# Final3_uptodate.net
KiCad netlist of a schematic drawn in EAGLE
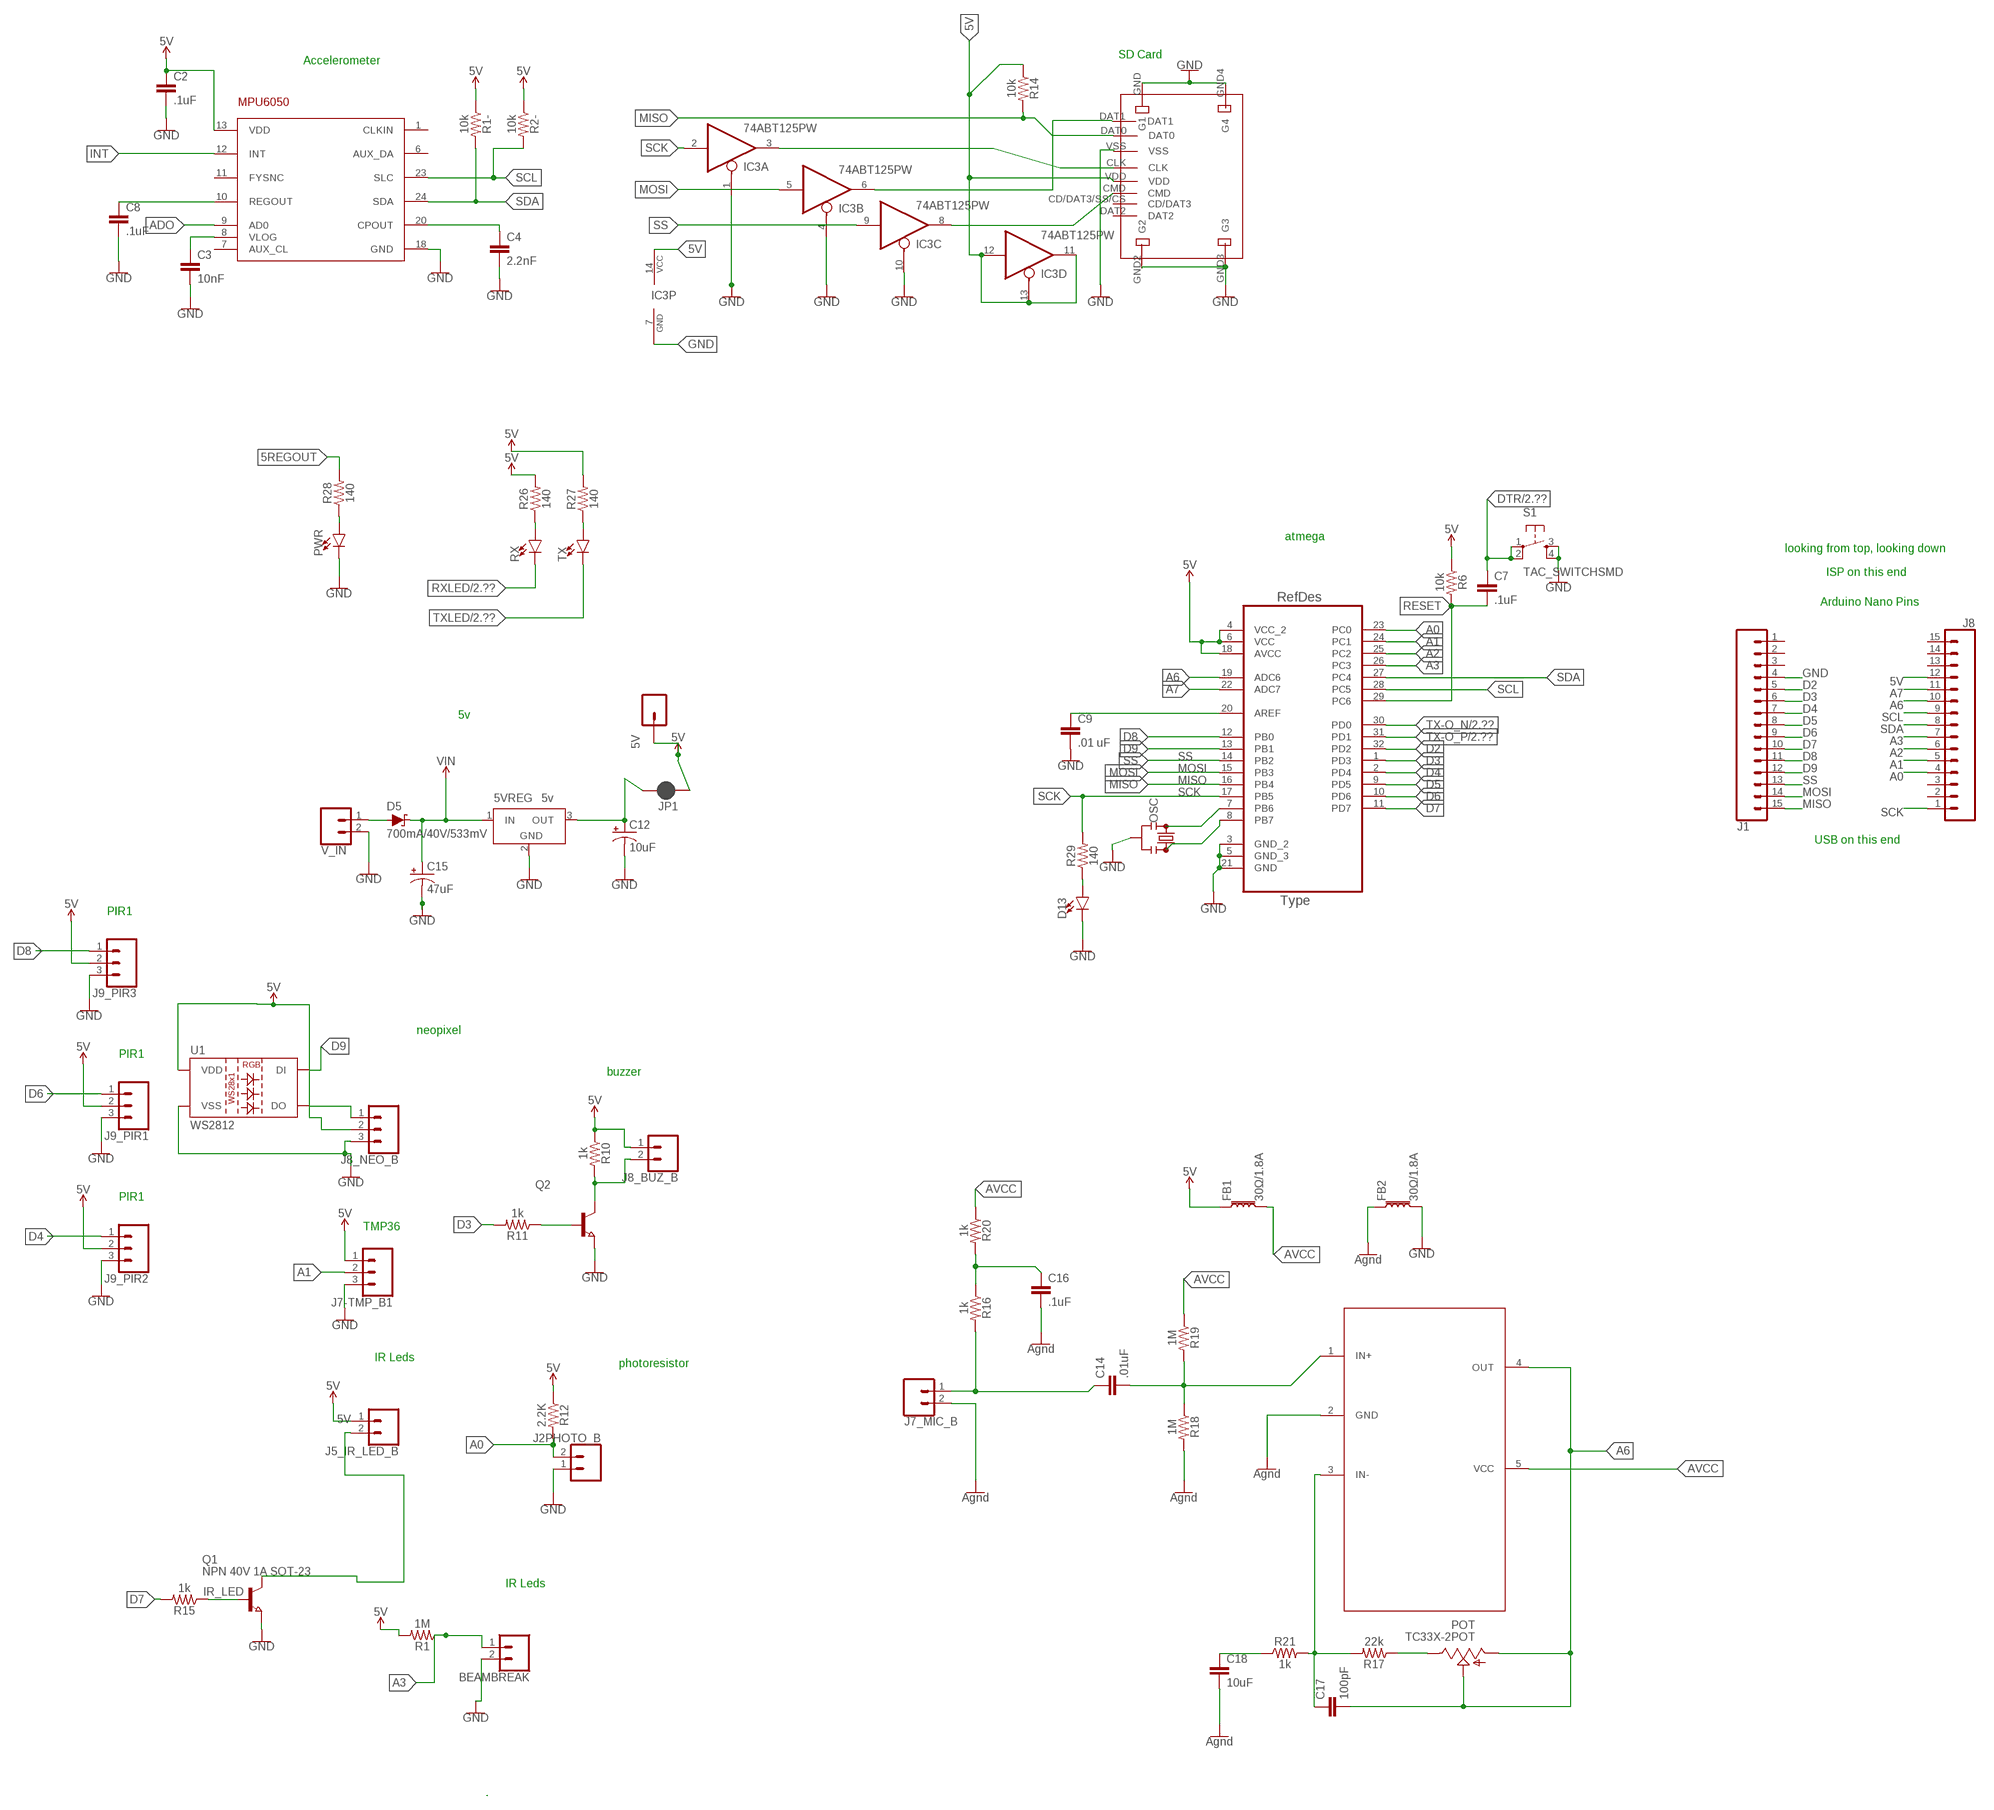
[diagram p0: schematic, sheet 1]
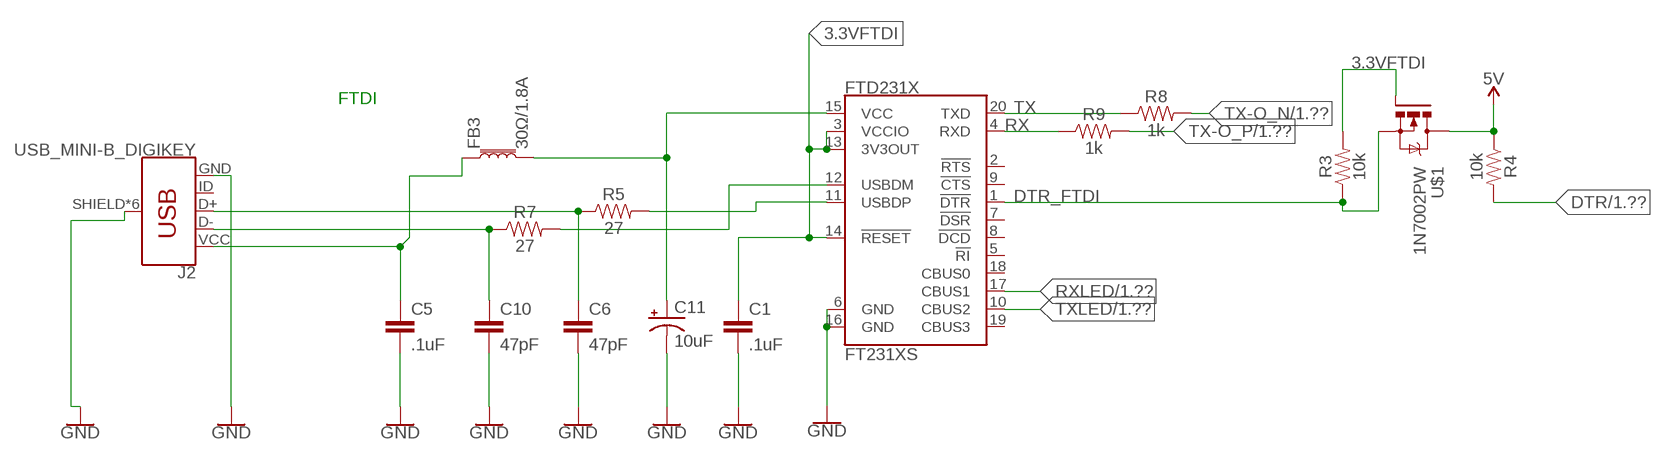
[diagram p1: schematic, sheet 2]

(export (version "E")
  (design (tool "Eeschema 10.0.6"))
  (components
    (comp (ref "5V")
      (value "CONN_01")
      (footprint "eagle-import:1X01")
      (libsource (lib "eagle-import") (part "CONN_01"))
    )
    (comp (ref "5VREG")
      (value "5v")
      (footprint "eagle-import:SOT223")
      (fields (field (name "MPN") "LT1129CST-5#PBF"))
      (libsource (lib "eagle-import") (part "LT1129CST5"))
    )
    (comp (ref "AMP")
      (value "MAX4466KS")
      (footprint "eagle-import:SC70-5")
      (libsource (lib "eagle-import") (part "MAX4466KS"))
    )
    (comp (ref "ATMEGA328P-AU")
      (value "ATMEGA328P-AU")
      (footprint "eagle-import:QFP80P900X900X120-32N")
      (libsource (lib "eagle-import") (part "ATMEGA328P-AU"))
    )
    (comp (ref "BEAMBREAK")
      (value "CONN_02LOCK")
      (footprint "eagle-import:1X02_LOCK")
      (libsource (lib "eagle-import") (part "CONN_02LOCK"))
    )
    (comp (ref "C2")
      (value ".1uF")
      (footprint "eagle-import:0402-CAP")
      (libsource (lib "eagle-import") (part ".22UF-CER"))
    )
    (comp (ref "C3")
      (value "10nF")
      (footprint "eagle-import:0402-CAP")
      (libsource (lib "eagle-import") (part ".22UF-CER"))
    )
    (comp (ref "C4")
      (value "2.2nF")
      (footprint "eagle-import:0402-CAP")
      (libsource (lib "eagle-import") (part ".22UF-CER"))
    )
    (comp (ref "C7")
      (value ".1uF")
      (footprint "eagle-import:0402-CAP")
      (libsource (lib "eagle-import") (part ".22UF-CER"))
    )
    (comp (ref "C8")
      (value ".1uF")
      (footprint "eagle-import:0402-CAP")
      (libsource (lib "eagle-import") (part ".22UF-CER"))
    )
    (comp (ref "C9")
      (value ".01 uF")
      (footprint "eagle-import:0402-CAP")
      (libsource (lib "eagle-import") (part ".22UF-CER"))
    )
    (comp (ref "C12")
      (value "10uF")
      (footprint "eagle-import:EIA3216")
      (libsource (lib "eagle-import") (part "10UF-TANT"))
    )
    (comp (ref "C14")
      (value ".01uF")
      (footprint "eagle-import:0402-CAP")
      (libsource (lib "eagle-import") (part ".22UF-CER"))
    )
    (comp (ref "C15")
      (value "47uF")
      (footprint "eagle-import:EIA3216")
      (libsource (lib "eagle-import") (part "10UF-TANT"))
    )
    (comp (ref "C16")
      (value ".1uF")
      (footprint "eagle-import:0402-CAP")
      (libsource (lib "eagle-import") (part ".22UF-CER"))
    )
    (comp (ref "C17")
      (value "100pF")
      (footprint "eagle-import:0402-CAP")
      (libsource (lib "eagle-import") (part ".22UF-CER"))
    )
    (comp (ref "C18")
      (value "10uF")
      (footprint "eagle-import:0402-CAP")
      (libsource (lib "eagle-import") (part ".22UF-CER"))
    )
    (comp (ref "D5")
      (value "700mA/40V/533mV")
      (footprint "eagle-import:SOT23-3")
      (libsource (lib "eagle-import") (part "DIODE-SCHOTTKY-ZLLS500"))
    )
    (comp (ref "D13")
      (value "LED0603")
      (footprint "eagle-import:LED-0603")
      (libsource (lib "eagle-import") (part "LED0603"))
    )
    (comp (ref "FB1")
      (value "30Ω/1.8A")
      (footprint "eagle-import:0603")
      (libsource (lib "eagle-import") (part "FERRITE_BEAD-0603"))
    )
    (comp (ref "FB2")
      (value "30Ω/1.8A")
      (footprint "eagle-import:0603")
      (libsource (lib "eagle-import") (part "FERRITE_BEAD-0603"))
    )
    (comp (ref "IC3")
      (value "74ABT125PW")
      (footprint "eagle-import:TSSOP14")
      (libsource (lib "eagle-import") (part "74125PWABT"))
    )
    (comp (ref "J1")
      (value "CONN_15")
      (footprint "eagle-import:1X15")
      (libsource (lib "eagle-import") (part "CONN_15"))
    )
    (comp (ref "J2PHOTO_B")
      (value "CONN_02LOCK")
      (footprint "eagle-import:1X02_LOCK")
      (libsource (lib "eagle-import") (part "CONN_02LOCK"))
    )
    (comp (ref "J5_IR_LED_B")
      (value "CONN_02LOCK")
      (footprint "eagle-import:1X02_LOCK")
      (libsource (lib "eagle-import") (part "CONN_02LOCK"))
    )
    (comp (ref "J7-TMP_B1")
      (value "CONN_03")
      (footprint "eagle-import:1X03")
      (libsource (lib "eagle-import") (part "CONN_03"))
    )
    (comp (ref "J7_MIC_B")
      (value "CONN_02LOCK")
      (footprint "eagle-import:1X02_LOCK")
      (libsource (lib "eagle-import") (part "CONN_02LOCK"))
    )
    (comp (ref "J8")
      (value "CONN_15")
      (footprint "eagle-import:1X15")
      (libsource (lib "eagle-import") (part "CONN_15"))
    )
    (comp (ref "J8_BUZ_B")
      (value "CONN_02LOCK")
      (footprint "eagle-import:1X02_LOCK")
      (libsource (lib "eagle-import") (part "CONN_02LOCK"))
    )
    (comp (ref "J8_NEO_B")
      (value "CONN_03")
      (footprint "eagle-import:1X03")
      (libsource (lib "eagle-import") (part "CONN_03"))
    )
    (comp (ref "J9_PIR1")
      (value "CONN_03")
      (footprint "eagle-import:1X03")
      (libsource (lib "eagle-import") (part "CONN_03"))
    )
    (comp (ref "J9_PIR2")
      (value "CONN_03")
      (footprint "eagle-import:1X03")
      (libsource (lib "eagle-import") (part "CONN_03"))
    )
    (comp (ref "J9_PIR3")
      (value "CONN_03")
      (footprint "eagle-import:1X03")
      (libsource (lib "eagle-import") (part "CONN_03"))
    )
    (comp (ref "JP1")
      (value "JUMPER-SMT_2_NC_PASTE")
      (footprint "eagle-import:SMT-JUMPER_2_NO_SILK")
      (libsource (lib "eagle-import") (part "JUMPER-SMT_2_NC_PASTE"))
    )
    (comp (ref "MPU6050")
      (value "MPU-6050")
      (footprint "eagle-import:QFN24-4X4")
      (libsource (lib "eagle-import") (part "MPU-6050"))
    )
    (comp (ref "OSC")
      (value "RESONATORSMD-3.2X1.3")
      (footprint "eagle-import:RESONATOR-SMD-3.2X1.3")
      (libsource (lib "eagle-import") (part "RESONATORSMD-3.2X1.3"))
    )
    (comp (ref "POT")
      (value "TC33X-2POT")
      (footprint "eagle-import:TC33X-2")
      (libsource (lib "eagle-import") (part "TC33X-2POT"))
    )
    (comp (ref "PWR")
      (value "LED0603")
      (footprint "eagle-import:LED-0603")
      (libsource (lib "eagle-import") (part "LED0603"))
    )
    (comp (ref "Q1")
      (value "NPN 40V 1A SOT-23")
      (footprint "eagle-import:SOT23")
      (libsource (lib "eagle-import") (part "NPN-TRANSISTOR_SOT23"))
    )
    (comp (ref "Q2")
      (value "NPN-TRANSISTOR_SOT23")
      (footprint "eagle-import:SOT23")
      (libsource (lib "eagle-import") (part "NPN-TRANSISTOR_SOT23"))
    )
    (comp (ref "R1")
      (value "1M")
      (footprint "eagle-import:0603")
      (libsource (lib "eagle-import") (part "0.05OHM-0603-1/5W-1%"))
    )
    (comp (ref "R1-")
      (value "10k")
      (footprint "eagle-import:0603")
      (libsource (lib "eagle-import") (part "0.05OHM-0603-1/5W-1%"))
    )
    (comp (ref "R2-")
      (value "10k")
      (footprint "eagle-import:0603")
      (libsource (lib "eagle-import") (part "0.05OHM-0603-1/5W-1%"))
    )
    (comp (ref "R6")
      (value "10k")
      (footprint "eagle-import:0603")
      (libsource (lib "eagle-import") (part "0.05OHM-0603-1/5W-1%"))
    )
    (comp (ref "R10")
      (value "1k")
      (footprint "eagle-import:0603")
      (libsource (lib "eagle-import") (part "0.05OHM-0603-1/5W-1%"))
    )
    (comp (ref "R11")
      (value "1k")
      (footprint "eagle-import:0603")
      (libsource (lib "eagle-import") (part "0.05OHM-0603-1/5W-1%"))
    )
    (comp (ref "R12")
      (value "2.2K")
      (footprint "eagle-import:0603")
      (libsource (lib "eagle-import") (part "0.05OHM-0603-1/5W-1%"))
    )
    (comp (ref "R14")
      (value "10k")
      (footprint "eagle-import:0603")
      (libsource (lib "eagle-import") (part "0.05OHM-0603-1/5W-1%"))
    )
    (comp (ref "R15")
      (value "1k")
      (footprint "eagle-import:0603")
      (libsource (lib "eagle-import") (part "0.05OHM-0603-1/5W-1%"))
    )
    (comp (ref "R16")
      (value "1k")
      (footprint "eagle-import:0603")
      (libsource (lib "eagle-import") (part "0.05OHM-0603-1/5W-1%"))
    )
    (comp (ref "R17")
      (value "22k")
      (footprint "eagle-import:0603")
      (libsource (lib "eagle-import") (part "0.05OHM-0603-1/5W-1%"))
    )
    (comp (ref "R18")
      (value "1M")
      (footprint "eagle-import:0603")
      (libsource (lib "eagle-import") (part "0.05OHM-0603-1/5W-1%"))
    )
    (comp (ref "R19")
      (value "1M")
      (footprint "eagle-import:0603")
      (libsource (lib "eagle-import") (part "0.05OHM-0603-1/5W-1%"))
    )
    (comp (ref "R20")
      (value "1k")
      (footprint "eagle-import:0603")
      (libsource (lib "eagle-import") (part "0.05OHM-0603-1/5W-1%"))
    )
    (comp (ref "R21")
      (value "1k")
      (footprint "eagle-import:0603")
      (libsource (lib "eagle-import") (part "0.05OHM-0603-1/5W-1%"))
    )
    (comp (ref "R26")
      (value "140")
      (footprint "eagle-import:0603")
      (libsource (lib "eagle-import") (part "2.2MOHM-1/10W-5%(0603)"))
    )
    (comp (ref "R27")
      (value "140")
      (footprint "eagle-import:0603")
      (libsource (lib "eagle-import") (part "2.2MOHM-1/10W-5%(0603)"))
    )
    (comp (ref "R28")
      (value "140")
      (footprint "eagle-import:0603")
      (libsource (lib "eagle-import") (part "2.2MOHM-1/10W-5%(0603)"))
    )
    (comp (ref "R29")
      (value "140")
      (footprint "eagle-import:0603")
      (libsource (lib "eagle-import") (part "2.2MOHM-1/10W-5%(0603)"))
    )
    (comp (ref "RX")
      (value "LED0603")
      (footprint "eagle-import:LED-0603")
      (libsource (lib "eagle-import") (part "LED0603"))
    )
    (comp (ref "S1")
      (value "TAC_SWITCHSMD")
      (footprint "eagle-import:TACTILE-SWITCH-SMD")
      (libsource (lib "eagle-import") (part "TAC_SWITCHSMD"))
    )
    (comp (ref "TX")
      (value "LED0603")
      (footprint "eagle-import:LED-0603")
      (libsource (lib "eagle-import") (part "LED0603"))
    )
    (comp (ref "U$2")
      (value "WM6698TR-ND_MICROSD")
      (footprint "eagle-import:MICROSD2")
      (libsource (lib "eagle-import") (part "WM6698TR-ND_MICROSD"))
    )
    (comp (ref "U1")
      (value "WS2812")
      (footprint "eagle-import:LED-TRICOLOR-5050-IC")
      (libsource (lib "eagle-import") (part "WS2812{dblquote}"))
    )
    (comp (ref "V_IN")
      (value "CONN_02LOCK")
      (footprint "eagle-import:1X02_LOCK")
      (libsource (lib "eagle-import") (part "CONN_02LOCK"))
    )
    (comp (ref "C1")
      (value ".1uF")
      (footprint "eagle-import:0402-CAP")
      (libsource (lib "eagle-import") (part ".22UF-CER"))
    )
    (comp (ref "C5")
      (value ".1uF")
      (footprint "eagle-import:0402-CAP")
      (libsource (lib "eagle-import") (part ".22UF-CER"))
    )
    (comp (ref "C6")
      (value "47pF")
      (footprint "eagle-import:0402-CAP")
      (libsource (lib "eagle-import") (part ".22UF-CER"))
    )
    (comp (ref "C10")
      (value "47pF")
      (footprint "eagle-import:0402-CAP")
      (libsource (lib "eagle-import") (part ".22UF-CER"))
    )
    (comp (ref "C11")
      (value "10uF")
      (footprint "eagle-import:EIA3216")
      (libsource (lib "eagle-import") (part "10UF-TANT"))
    )
    (comp (ref "FB3")
      (value "30Ω/1.8A")
      (footprint "eagle-import:0603")
      (libsource (lib "eagle-import") (part "FERRITE_BEAD-0603"))
    )
    (comp (ref "FTD231X")
      (value "FT231XS")
      (footprint "eagle-import:SSOP20_L")
      (libsource (lib "eagle-import") (part "FT231XS"))
    )
    (comp (ref "J2")
      (value "USB_MINI-B_DIGIKEY")
      (footprint "eagle-import:MICRO-USB-DIGIKEY-FCI2")
      (libsource (lib "eagle-import") (part "USB_MINI-B_DIGIKEY"))
    )
    (comp (ref "R3")
      (value "10k")
      (footprint "eagle-import:0603")
      (libsource (lib "eagle-import") (part "0.05OHM-0603-1/5W-1%"))
    )
    (comp (ref "R4")
      (value "10k")
      (footprint "eagle-import:0603")
      (libsource (lib "eagle-import") (part "0.05OHM-0603-1/5W-1%"))
    )
    (comp (ref "R5")
      (value "27")
      (footprint "eagle-import:0603")
      (libsource (lib "eagle-import") (part "0.05OHM-0603-1/5W-1%"))
    )
    (comp (ref "R7")
      (value "27")
      (footprint "eagle-import:0603")
      (libsource (lib "eagle-import") (part "0.05OHM-0603-1/5W-1%"))
    )
    (comp (ref "R8")
      (value "1k")
      (footprint "eagle-import:0603")
      (libsource (lib "eagle-import") (part "0.05OHM-0603-1/5W-1%"))
    )
    (comp (ref "R9")
      (value "1k")
      (footprint "eagle-import:0603")
      (libsource (lib "eagle-import") (part "0.05OHM-0603-1/5W-1%"))
    )
    (comp (ref "U$1")
      (value "1N7002PW")
      (footprint "eagle-import:SOT323W_INFINEON")
      (libsource (lib "eagle-import") (part "1N7002PW"))
    )
  )
  (nets
    (net (code "1") (name "3.3VFTDI") (class "Default")
      (node (ref "C1") (pin "1") (pinfunction "1_1") (pintype "passive"))
      (node (ref "FTD231X") (pin "13") (pinfunction "3V3OUT_13") (pintype "bidirectional"))
      (node (ref "FTD231X") (pin "14") (pinfunction "~{RESET}_14") (pintype "bidirectional"))
      (node (ref "FTD231X") (pin "3") (pinfunction "VCCIO_3") (pintype "bidirectional"))
      (node (ref "R3") (pin "2") (pinfunction "2_2") (pintype "passive"))
      (node (ref "U$1") (pin "1") (pinfunction "G_1") (pintype "passive"))
    )
    (net (code "2") (name "5REGOUT") (class "Default")
      (node (ref "5VREG") (pin "3") (pinfunction "OUT_3") (pintype "output"))
      (node (ref "C12") (pin "A") (pinfunction "+_A") (pintype "passive"))
      (node (ref "JP1") (pin "P$1") (pinfunction "2_P$1") (pintype "passive"))
      (node (ref "R28") (pin "2") (pinfunction "2_2") (pintype "passive"))
    )
    (net (code "3") (name "5V") (class "Default")
      (node (ref "5V") (pin "1") (pinfunction "1_1") (pintype "passive"))
      (node (ref "ATMEGA328P-AU") (pin "18") (pinfunction "AVCC_18") (pintype "power_in"))
      (node (ref "ATMEGA328P-AU") (pin "4") (pinfunction "VCC_2_4") (pintype "power_in"))
      (node (ref "ATMEGA328P-AU") (pin "6") (pinfunction "VCC_6") (pintype "power_in"))
      (node (ref "C2") (pin "1") (pinfunction "1_1") (pintype "passive"))
      (node (ref "FB1") (pin "1") (pinfunction "1_1") (pintype "passive"))
      (node (ref "IC3") (pin "11") (pinfunction "O_11") (pintype "tri_state"))
      (node (ref "IC3") (pin "12") (pinfunction "I_12") (pintype "input"))
      (node (ref "IC3") (pin "13") (pinfunction "OE_13") (pintype "input"))
      (node (ref "IC3") (pin "14") (pinfunction "VCC_14") (pintype "power_in"))
      (node (ref "J5_IR_LED_B") (pin "1") (pinfunction "1_1") (pintype "passive"))
      (node (ref "J7-TMP_B1") (pin "1") (pinfunction "1_1") (pintype "passive"))
      (node (ref "J8") (pin "12") (pinfunction "12_12") (pintype "passive"))
      (node (ref "J8_BUZ_B") (pin "1") (pinfunction "1_1") (pintype "passive"))
      (node (ref "J8_NEO_B") (pin "2") (pinfunction "2_2") (pintype "passive"))
      (node (ref "J9_PIR1") (pin "2") (pinfunction "2_2") (pintype "passive"))
      (node (ref "J9_PIR2") (pin "2") (pinfunction "2_2") (pintype "passive"))
      (node (ref "J9_PIR3") (pin "2") (pinfunction "2_2") (pintype "passive"))
      (node (ref "JP1") (pin "2") (pinfunction "1_2") (pintype "passive"))
      (node (ref "MPU6050") (pin "13") (pinfunction "VDD_13") (pintype "bidirectional"))
      (node (ref "R1") (pin "2") (pinfunction "2_2") (pintype "passive"))
      (node (ref "R1-") (pin "1") (pinfunction "1_1") (pintype "passive"))
      (node (ref "R10") (pin "1") (pinfunction "1_1") (pintype "passive"))
      (node (ref "R12") (pin "1") (pinfunction "1_1") (pintype "passive"))
      (node (ref "R14") (pin "1") (pinfunction "1_1") (pintype "passive"))
      (node (ref "R2-") (pin "1") (pinfunction "1_1") (pintype "passive"))
      (node (ref "R26") (pin "2") (pinfunction "2_2") (pintype "passive"))
      (node (ref "R27") (pin "2") (pinfunction "2_2") (pintype "passive"))
      (node (ref "R4") (pin "1") (pinfunction "1_1") (pintype "passive"))
      (node (ref "R6") (pin "1") (pinfunction "1_1") (pintype "passive"))
      (node (ref "U$1") (pin "3") (pinfunction "D_3") (pintype "passive"))
      (node (ref "U$2") (pin "VDD") (pinfunction "VDD_VDD") (pintype "bidirectional"))
      (node (ref "U1") (pin "3") (pinfunction "VDD_3") (pintype "bidirectional"))
      (node (ref "U1") (pin "5") (pinfunction "VDD_5") (pintype "bidirectional"))
    )
    (net (code "4") (name "A0") (class "Default")
      (node (ref "ATMEGA328P-AU") (pin "23") (pinfunction "PC0_23") (pintype "bidirectional"))
      (node (ref "J2PHOTO_B") (pin "2") (pinfunction "2_2") (pintype "passive"))
      (node (ref "J8") (pin "4") (pinfunction "4_4") (pintype "passive"))
      (node (ref "R12") (pin "2") (pinfunction "2_2") (pintype "passive"))
    )
    (net (code "5") (name "A1") (class "Default")
      (node (ref "ATMEGA328P-AU") (pin "24") (pinfunction "PC1_24") (pintype "bidirectional"))
      (node (ref "J7-TMP_B1") (pin "2") (pinfunction "2_2") (pintype "passive"))
      (node (ref "J8") (pin "5") (pinfunction "5_5") (pintype "passive"))
    )
    (net (code "6") (name "A2") (class "Default")
      (node (ref "ATMEGA328P-AU") (pin "25") (pinfunction "PC2_25") (pintype "bidirectional"))
      (node (ref "J8") (pin "6") (pinfunction "6_6") (pintype "passive"))
    )
    (net (code "7") (name "A3") (class "Default")
      (node (ref "ATMEGA328P-AU") (pin "26") (pinfunction "PC3_26") (pintype "bidirectional"))
      (node (ref "BEAMBREAK") (pin "1") (pinfunction "1_1") (pintype "passive"))
      (node (ref "J8") (pin "7") (pinfunction "7_7") (pintype "passive"))
      (node (ref "R1") (pin "1") (pinfunction "1_1") (pintype "passive"))
    )
    (net (code "8") (name "A6") (class "Default")
      (node (ref "AMP") (pin "4") (pinfunction "OUT_4") (pintype "bidirectional"))
      (node (ref "ATMEGA328P-AU") (pin "19") (pinfunction "ADC6_19") (pintype "input"))
      (node (ref "C17") (pin "2") (pinfunction "2_2") (pintype "passive"))
      (node (ref "J8") (pin "10") (pinfunction "10_10") (pintype "passive"))
      (node (ref "POT") (pin "2") (pinfunction "2_2") (pintype "passive"))
      (node (ref "POT") (pin "3") (pinfunction "3_3") (pintype "passive"))
    )
    (net (code "9") (name "A7") (class "Default")
      (node (ref "ATMEGA328P-AU") (pin "22") (pinfunction "ADC7_22") (pintype "input"))
      (node (ref "J8") (pin "11") (pinfunction "11_11") (pintype "passive"))
    )
    (net (code "10") (name "ADO") (class "Default")
      (node (ref "MPU6050") (pin "9") (pinfunction "AD0_9") (pintype "bidirectional"))
    )
    (net (code "11") (name "AVCC") (class "Default")
      (node (ref "AMP") (pin "5") (pinfunction "VCC_5") (pintype "bidirectional"))
      (node (ref "FB1") (pin "2") (pinfunction "2_2") (pintype "passive"))
      (node (ref "R19") (pin "1") (pinfunction "1_1") (pintype "passive"))
      (node (ref "R20") (pin "1") (pinfunction "1_1") (pintype "passive"))
    )
    (net (code "12") (name "D2") (class "Default")
      (node (ref "ATMEGA328P-AU") (pin "32") (pinfunction "PD2_32") (pintype "bidirectional"))
      (node (ref "J1") (pin "5") (pinfunction "5_5") (pintype "passive"))
    )
    (net (code "13") (name "D3") (class "Default")
      (node (ref "ATMEGA328P-AU") (pin "1") (pinfunction "PD3_1") (pintype "bidirectional"))
      (node (ref "J1") (pin "6") (pinfunction "6_6") (pintype "passive"))
      (node (ref "R11") (pin "2") (pinfunction "2_2") (pintype "passive"))
    )
    (net (code "14") (name "D4") (class "Default")
      (node (ref "ATMEGA328P-AU") (pin "2") (pinfunction "PD4_2") (pintype "bidirectional"))
      (node (ref "J1") (pin "7") (pinfunction "7_7") (pintype "passive"))
      (node (ref "J9_PIR2") (pin "1") (pinfunction "1_1") (pintype "passive"))
    )
    (net (code "15") (name "D5") (class "Default")
      (node (ref "ATMEGA328P-AU") (pin "9") (pinfunction "PD5_9") (pintype "bidirectional"))
      (node (ref "J1") (pin "8") (pinfunction "8_8") (pintype "passive"))
    )
    (net (code "16") (name "D6") (class "Default")
      (node (ref "ATMEGA328P-AU") (pin "10") (pinfunction "PD6_10") (pintype "bidirectional"))
      (node (ref "J1") (pin "9") (pinfunction "9_9") (pintype "passive"))
      (node (ref "J9_PIR1") (pin "1") (pinfunction "1_1") (pintype "passive"))
    )
    (net (code "17") (name "D7") (class "Default")
      (node (ref "ATMEGA328P-AU") (pin "11") (pinfunction "PD7_11") (pintype "bidirectional"))
      (node (ref "J1") (pin "10") (pinfunction "10_10") (pintype "passive"))
      (node (ref "R15") (pin "2") (pinfunction "2_2") (pintype "passive"))
    )
    (net (code "18") (name "D8") (class "Default")
      (node (ref "ATMEGA328P-AU") (pin "12") (pinfunction "PB0_12") (pintype "bidirectional"))
      (node (ref "J1") (pin "11") (pinfunction "11_11") (pintype "passive"))
      (node (ref "J9_PIR3") (pin "1") (pinfunction "1_1") (pintype "passive"))
    )
    (net (code "19") (name "D9") (class "Default")
      (node (ref "ATMEGA328P-AU") (pin "13") (pinfunction "PB1_13") (pintype "bidirectional"))
      (node (ref "J1") (pin "12") (pinfunction "12_12") (pintype "passive"))
      (node (ref "U1") (pin "2") (pinfunction "DI_2") (pintype "bidirectional"))
    )
    (net (code "20") (name "DTR") (class "Default")
      (node (ref "C7") (pin "1") (pinfunction "1_1") (pintype "passive"))
      (node (ref "R4") (pin "2") (pinfunction "2_2") (pintype "passive"))
      (node (ref "S1") (pin "1") (pinfunction "1_1") (pintype "passive"))
      (node (ref "S1") (pin "2") (pinfunction "2_2") (pintype "passive"))
    )
    (net (code "21") (name "DTR_FTDI") (class "Default")
      (node (ref "FTD231X") (pin "1") (pinfunction "~{DTR}_1") (pintype "bidirectional"))
      (node (ref "R3") (pin "1") (pinfunction "1_1") (pintype "passive"))
      (node (ref "U$1") (pin "2") (pinfunction "S_2") (pintype "passive"))
    )
    (net (code "22") (name "GND") (class "Default")
      (node (ref "5VREG") (pin "2") (pinfunction "GND_2") (pintype "power_in"))
      (node (ref "AMP") (pin "2") (pinfunction "GND_2") (pintype "bidirectional"))
      (node (ref "ATMEGA328P-AU") (pin "21") (pinfunction "GND_21") (pintype "passive"))
      (node (ref "ATMEGA328P-AU") (pin "3") (pinfunction "GND_2_3") (pintype "passive"))
      (node (ref "ATMEGA328P-AU") (pin "5") (pinfunction "GND_3_5") (pintype "passive"))
      (node (ref "BEAMBREAK") (pin "2") (pinfunction "2_2") (pintype "passive"))
      (node (ref "C1") (pin "2") (pinfunction "2_2") (pintype "passive"))
      (node (ref "C10") (pin "2") (pinfunction "2_2") (pintype "passive"))
      (node (ref "C11") (pin "C") (pinfunction "-_C") (pintype "passive"))
      (node (ref "C12") (pin "C") (pinfunction "-_C") (pintype "passive"))
      (node (ref "C15") (pin "C") (pinfunction "-_C") (pintype "passive"))
      (node (ref "C16") (pin "2") (pinfunction "2_2") (pintype "passive"))
      (node (ref "C18") (pin "2") (pinfunction "2_2") (pintype "passive"))
      (node (ref "C2") (pin "2") (pinfunction "2_2") (pintype "passive"))
      (node (ref "C3") (pin "2") (pinfunction "2_2") (pintype "passive"))
      (node (ref "C4") (pin "2") (pinfunction "2_2") (pintype "passive"))
      (node (ref "C5") (pin "2") (pinfunction "2_2") (pintype "passive"))
      (node (ref "C6") (pin "2") (pinfunction "2_2") (pintype "passive"))
      (node (ref "C8") (pin "2") (pinfunction "2_2") (pintype "passive"))
      (node (ref "C9") (pin "2") (pinfunction "2_2") (pintype "passive"))
      (node (ref "D13") (pin "C") (pinfunction "C_C") (pintype "passive"))
      (node (ref "FB2") (pin "1") (pinfunction "1_1") (pintype "passive"))
      (node (ref "FB2") (pin "2") (pinfunction "2_2") (pintype "passive"))
      (node (ref "FTD231X") (pin "16") (pinfunction "GND_16") (pintype "bidirectional"))
      (node (ref "FTD231X") (pin "6") (pinfunction "GND_6") (pintype "bidirectional"))
      (node (ref "IC3") (pin "1") (pinfunction "OE_1") (pintype "input"))
      (node (ref "IC3") (pin "10") (pinfunction "OE_10") (pintype "input"))
      (node (ref "IC3") (pin "4") (pinfunction "OE_4") (pintype "input"))
      (node (ref "IC3") (pin "7") (pinfunction "GND_7") (pintype "power_in"))
      (node (ref "J1") (pin "4") (pinfunction "4_4") (pintype "passive"))
      (node (ref "J2") (pin "GND") (pinfunction "GND_GND") (pintype "power_in"))
      (node (ref "J2") (pin "SHIELD") (pinfunction "SHIELD_SHIELD") (pintype "bidirectional"))
      (node (ref "J2") (pin "SHIELD1") (pinfunction "SHIELD_SHIELD1") (pintype "bidirectional"))
      (node (ref "J2") (pin "SHIELD2") (pinfunction "SHIELD_SHIELD2") (pintype "bidirectional"))
      (node (ref "J2") (pin "SHIELD3") (pinfunction "SHIELD_SHIELD3") (pintype "bidirectional"))
      (node (ref "J2") (pin "SHIELD4") (pinfunction "SHIELD_SHIELD4") (pintype "bidirectional"))
      (node (ref "J2") (pin "SHIELD5") (pinfunction "SHIELD_SHIELD5") (pintype "bidirectional"))
      (node (ref "J2PHOTO_B") (pin "1") (pinfunction "1_1") (pintype "passive"))
      (node (ref "J7-TMP_B1") (pin "3") (pinfunction "3_3") (pintype "passive"))
      (node (ref "J7_MIC_B") (pin "2") (pinfunction "2_2") (pintype "passive"))
      (node (ref "J8_NEO_B") (pin "3") (pinfunction "3_3") (pintype "passive"))
      (node (ref "J9_PIR1") (pin "3") (pinfunction "3_3") (pintype "passive"))
      (node (ref "J9_PIR2") (pin "3") (pinfunction "3_3") (pintype "passive"))
      (node (ref "J9_PIR3") (pin "3") (pinfunction "3_3") (pintype "passive"))
      (node (ref "MPU6050") (pin "18") (pinfunction "GND_18") (pintype "bidirectional"))
      (node (ref "OSC") (pin "2") (pinfunction "2_2") (pintype "passive"))
      (node (ref "PWR") (pin "C") (pinfunction "C_C") (pintype "passive"))
      (node (ref "Q1") (pin "2") (pinfunction "E_2") (pintype "passive"))
      (node (ref "Q2") (pin "2") (pinfunction "E_2") (pintype "passive"))
      (node (ref "R18") (pin "2") (pinfunction "2_2") (pintype "passive"))
      (node (ref "S1") (pin "3") (pinfunction "3_3") (pintype "passive"))
      (node (ref "S1") (pin "4") (pinfunction "4_4") (pintype "passive"))
      (node (ref "U$2") (pin "GND") (pinfunction "G1_GND") (pintype "bidirectional"))
      (node (ref "U$2") (pin "GND2") (pinfunction "G2_GND2") (pintype "bidirectional"))
      (node (ref "U$2") (pin "GND3") (pinfunction "G3_GND3") (pintype "bidirectional"))
      (node (ref "U$2") (pin "GND4") (pinfunction "G4_GND4") (pintype "bidirectional"))
      (node (ref "U$2") (pin "VSS") (pinfunction "VSS_VSS") (pintype "bidirectional"))
      (node (ref "U1") (pin "6") (pinfunction "VSS_6") (pintype "bidirectional"))
      (node (ref "V_IN") (pin "2") (pinfunction "2_2") (pintype "passive"))
    )
    (net (code "23") (name "INT") (class "Default")
      (node (ref "MPU6050") (pin "12") (pinfunction "INT_12") (pintype "bidirectional"))
    )
    (net (code "24") (name "IR_LED") (class "Default")
      (node (ref "Q1") (pin "1") (pinfunction "B_1") (pintype "passive"))
      (node (ref "R15") (pin "1") (pinfunction "1_1") (pintype "passive"))
    )
    (net (code "25") (name "MISO") (class "Default")
      (node (ref "ATMEGA328P-AU") (pin "16") (pinfunction "PB4_16") (pintype "bidirectional"))
      (node (ref "J1") (pin "15") (pinfunction "15_15") (pintype "passive"))
      (node (ref "R14") (pin "2") (pinfunction "2_2") (pintype "passive"))
      (node (ref "U$2") (pin "DAT0") (pinfunction "DAT0_DAT0") (pintype "bidirectional"))
    )
    (net (code "26") (name "MOSI") (class "Default")
      (node (ref "ATMEGA328P-AU") (pin "15") (pinfunction "PB3_15") (pintype "bidirectional"))
      (node (ref "IC3") (pin "5") (pinfunction "I_5") (pintype "input"))
      (node (ref "J1") (pin "14") (pinfunction "14_14") (pintype "passive"))
    )
    (net (code "27") (name "Net-(AMP-IN+)") (class "Default")
      (node (ref "AMP") (pin "1") (pinfunction "IN+_1") (pintype "bidirectional"))
      (node (ref "C14") (pin "2") (pinfunction "2_2") (pintype "passive"))
      (node (ref "R18") (pin "1") (pinfunction "1_1") (pintype "passive"))
      (node (ref "R19") (pin "2") (pinfunction "2_2") (pintype "passive"))
    )
    (net (code "28") (name "Net-(AMP-IN-)") (class "Default")
      (node (ref "AMP") (pin "3") (pinfunction "IN-_3") (pintype "bidirectional"))
      (node (ref "C17") (pin "1") (pinfunction "1_1") (pintype "passive"))
      (node (ref "R17") (pin "2") (pinfunction "2_2") (pintype "passive"))
      (node (ref "R21") (pin "2") (pinfunction "2_2") (pintype "passive"))
    )
    (net (code "29") (name "Net-(ATMEGA328P-AU-AREF)") (class "Default")
      (node (ref "ATMEGA328P-AU") (pin "20") (pinfunction "AREF_20") (pintype "input"))
      (node (ref "C9") (pin "1") (pinfunction "1_1") (pintype "passive"))
    )
    (net (code "30") (name "Net-(ATMEGA328P-AU-PB6)") (class "Default")
      (node (ref "ATMEGA328P-AU") (pin "7") (pinfunction "PB6_7") (pintype "bidirectional"))
      (node (ref "OSC") (pin "1") (pinfunction "1_1") (pintype "passive"))
    )
    (net (code "31") (name "Net-(ATMEGA328P-AU-PB7)") (class "Default")
      (node (ref "ATMEGA328P-AU") (pin "8") (pinfunction "PB7_8") (pintype "bidirectional"))
      (node (ref "OSC") (pin "3") (pinfunction "3_3") (pintype "passive"))
    )
    (net (code "32") (name "Net-(C6-Pad1)") (class "Default")
      (node (ref "C6") (pin "1") (pinfunction "1_1") (pintype "passive"))
      (node (ref "J2") (pin "D+") (pinfunction "D+_D+") (pintype "bidirectional"))
      (node (ref "R5") (pin "1") (pinfunction "1_1") (pintype "passive"))
    )
    (net (code "33") (name "Net-(C10-Pad1)") (class "Default")
      (node (ref "C10") (pin "1") (pinfunction "1_1") (pintype "passive"))
      (node (ref "J2") (pin "D-") (pinfunction "D-_D-") (pintype "bidirectional"))
      (node (ref "R7") (pin "1") (pinfunction "1_1") (pintype "passive"))
    )
    (net (code "34") (name "Net-(C14-Pad1)") (class "Default")
      (node (ref "C14") (pin "1") (pinfunction "1_1") (pintype "passive"))
      (node (ref "J7_MIC_B") (pin "1") (pinfunction "1_1") (pintype "passive"))
      (node (ref "R16") (pin "2") (pinfunction "2_2") (pintype "passive"))
    )
    (net (code "35") (name "Net-(C16-Pad1)") (class "Default")
      (node (ref "C16") (pin "1") (pinfunction "1_1") (pintype "passive"))
      (node (ref "R16") (pin "1") (pinfunction "1_1") (pintype "passive"))
      (node (ref "R20") (pin "2") (pinfunction "2_2") (pintype "passive"))
    )
    (net (code "36") (name "Net-(C18-Pad1)") (class "Default")
      (node (ref "C18") (pin "1") (pinfunction "1_1") (pintype "passive"))
      (node (ref "R21") (pin "1") (pinfunction "1_1") (pintype "passive"))
    )
    (net (code "37") (name "Net-(D5-A)") (class "Default")
      (node (ref "D5") (pin "1") (pinfunction "A_1") (pintype "passive"))
      (node (ref "V_IN") (pin "1") (pinfunction "1_1") (pintype "passive"))
    )
    (net (code "38") (name "Net-(D13-PadA)") (class "Default")
      (node (ref "D13") (pin "A") (pinfunction "A_A") (pintype "passive"))
      (node (ref "R29") (pin "1") (pinfunction "1_1") (pintype "passive"))
    )
    (net (code "39") (name "Net-(FTD231X-USBDM)") (class "Default")
      (node (ref "FTD231X") (pin "12") (pinfunction "USBDM_12") (pintype "bidirectional"))
      (node (ref "R7") (pin "2") (pinfunction "2_2") (pintype "passive"))
    )
    (net (code "40") (name "Net-(FTD231X-USBDP)") (class "Default")
      (node (ref "FTD231X") (pin "11") (pinfunction "USBDP_11") (pintype "bidirectional"))
      (node (ref "R5") (pin "2") (pinfunction "2_2") (pintype "passive"))
    )
    (net (code "41") (name "Net-(IC3A-O)") (class "Default")
      (node (ref "IC3") (pin "3") (pinfunction "O_3") (pintype "tri_state"))
      (node (ref "U$2") (pin "CLK") (pinfunction "CLK_CLK") (pintype "bidirectional"))
    )
    (net (code "42") (name "Net-(IC3B-O)") (class "Default")
      (node (ref "IC3") (pin "6") (pinfunction "O_6") (pintype "tri_state"))
      (node (ref "U$2") (pin "DAT1") (pinfunction "DAT1_DAT1") (pintype "bidirectional"))
    )
    (net (code "43") (name "Net-(IC3C-O)") (class "Default")
      (node (ref "IC3") (pin "8") (pinfunction "O_8") (pintype "tri_state"))
      (node (ref "U$2") (pin "CMD") (pinfunction "CMD_CMD") (pintype "bidirectional"))
    )
    (net (code "44") (name "Net-(MPU6050-CPOUT)") (class "Default")
      (node (ref "C4") (pin "1") (pinfunction "1_1") (pintype "passive"))
      (node (ref "MPU6050") (pin "20") (pinfunction "CPOUT_20") (pintype "bidirectional"))
    )
    (net (code "45") (name "Net-(MPU6050-REGOUT)") (class "Default")
      (node (ref "C8") (pin "1") (pinfunction "1_1") (pintype "passive"))
      (node (ref "MPU6050") (pin "10") (pinfunction "REGOUT_10") (pintype "bidirectional"))
    )
    (net (code "46") (name "Net-(MPU6050-VLOG)") (class "Default")
      (node (ref "C3") (pin "1") (pinfunction "1_1") (pintype "passive"))
      (node (ref "MPU6050") (pin "8") (pinfunction "VLOG_8") (pintype "bidirectional"))
    )
    (net (code "47") (name "Net-(POT-Pad1)") (class "Default")
      (node (ref "POT") (pin "1") (pinfunction "1_1") (pintype "passive"))
      (node (ref "R17") (pin "1") (pinfunction "1_1") (pintype "passive"))
    )
    (net (code "48") (name "Net-(PWR-PadA)") (class "Default")
      (node (ref "PWR") (pin "A") (pinfunction "A_A") (pintype "passive"))
      (node (ref "R28") (pin "1") (pinfunction "1_1") (pintype "passive"))
    )
    (net (code "49") (name "Net-(Q1-C)") (class "Default")
      (node (ref "J5_IR_LED_B") (pin "2") (pinfunction "2_2") (pintype "passive"))
      (node (ref "Q1") (pin "3") (pinfunction "C_3") (pintype "passive"))
    )
    (net (code "50") (name "Net-(Q2-B)") (class "Default")
      (node (ref "Q2") (pin "1") (pinfunction "B_1") (pintype "passive"))
      (node (ref "R11") (pin "1") (pinfunction "1_1") (pintype "passive"))
    )
    (net (code "51") (name "Net-(Q2-C)") (class "Default")
      (node (ref "J8_BUZ_B") (pin "2") (pinfunction "2_2") (pintype "passive"))
      (node (ref "Q2") (pin "3") (pinfunction "C_3") (pintype "passive"))
      (node (ref "R10") (pin "2") (pinfunction "2_2") (pintype "passive"))
    )
    (net (code "52") (name "Net-(R26-Pad1)") (class "Default")
      (node (ref "R26") (pin "1") (pinfunction "1_1") (pintype "passive"))
      (node (ref "RX") (pin "A") (pinfunction "A_A") (pintype "passive"))
    )
    (net (code "53") (name "Net-(R27-Pad1)") (class "Default")
      (node (ref "R27") (pin "1") (pinfunction "1_1") (pintype "passive"))
      (node (ref "TX") (pin "A") (pinfunction "A_A") (pintype "passive"))
    )
    (net (code "54") (name "Net-(U1-DO)") (class "Default")
      (node (ref "J8_NEO_B") (pin "1") (pinfunction "1_1") (pintype "passive"))
      (node (ref "U1") (pin "1") (pinfunction "DO_1") (pintype "bidirectional"))
    )
    (net (code "55") (name "RESET") (class "Default")
      (node (ref "ATMEGA328P-AU") (pin "29") (pinfunction "PC6_29") (pintype "bidirectional"))
      (node (ref "C7") (pin "2") (pinfunction "2_2") (pintype "passive"))
      (node (ref "R6") (pin "2") (pinfunction "2_2") (pintype "passive"))
    )
    (net (code "56") (name "RX") (class "Default")
      (node (ref "FTD231X") (pin "4") (pinfunction "RXD_4") (pintype "bidirectional"))
      (node (ref "R9") (pin "1") (pinfunction "1_1") (pintype "passive"))
    )
    (net (code "57") (name "RXLED") (class "Default")
      (node (ref "FTD231X") (pin "17") (pinfunction "CBUS1_17") (pintype "bidirectional"))
      (node (ref "RX") (pin "C") (pinfunction "C_C") (pintype "passive"))
    )
    (net (code "58") (name "SCK") (class "Default")
      (node (ref "ATMEGA328P-AU") (pin "17") (pinfunction "PB5_17") (pintype "bidirectional"))
      (node (ref "IC3") (pin "2") (pinfunction "I_2") (pintype "input"))
      (node (ref "J8") (pin "1") (pinfunction "1_1") (pintype "passive"))
      (node (ref "R29") (pin "2") (pinfunction "2_2") (pintype "passive"))
    )
    (net (code "59") (name "SCL") (class "Default")
      (node (ref "ATMEGA328P-AU") (pin "28") (pinfunction "PC5_28") (pintype "bidirectional"))
      (node (ref "J8") (pin "9") (pinfunction "9_9") (pintype "passive"))
      (node (ref "MPU6050") (pin "23") (pinfunction "SLC_23") (pintype "bidirectional"))
      (node (ref "R2-") (pin "2") (pinfunction "2_2") (pintype "passive"))
    )
    (net (code "60") (name "SDA") (class "Default")
      (node (ref "ATMEGA328P-AU") (pin "27") (pinfunction "PC4_27") (pintype "bidirectional"))
      (node (ref "J8") (pin "8") (pinfunction "8_8") (pintype "passive"))
      (node (ref "MPU6050") (pin "24") (pinfunction "SDA_24") (pintype "bidirectional"))
      (node (ref "R1-") (pin "2") (pinfunction "2_2") (pintype "passive"))
    )
    (net (code "61") (name "SS") (class "Default")
      (node (ref "ATMEGA328P-AU") (pin "14") (pinfunction "PB2_14") (pintype "bidirectional"))
      (node (ref "IC3") (pin "9") (pinfunction "I_9") (pintype "input"))
      (node (ref "J1") (pin "13") (pinfunction "13_13") (pintype "passive"))
    )
    (net (code "62") (name "TX") (class "Default")
      (node (ref "FTD231X") (pin "20") (pinfunction "TXD_20") (pintype "bidirectional"))
      (node (ref "R8") (pin "1") (pinfunction "1_1") (pintype "passive"))
    )
    (net (code "63") (name "TX-O_N") (class "Default")
      (node (ref "ATMEGA328P-AU") (pin "30") (pinfunction "PD0_30") (pintype "bidirectional"))
      (node (ref "R8") (pin "2") (pinfunction "2_2") (pintype "passive"))
    )
    (net (code "64") (name "TX-O_P") (class "Default")
      (node (ref "ATMEGA328P-AU") (pin "31") (pinfunction "PD1_31") (pintype "bidirectional"))
      (node (ref "R9") (pin "2") (pinfunction "2_2") (pintype "passive"))
    )
    (net (code "65") (name "TXLED") (class "Default")
      (node (ref "FTD231X") (pin "10") (pinfunction "CBUS2_10") (pintype "bidirectional"))
      (node (ref "TX") (pin "C") (pinfunction "C_C") (pintype "passive"))
    )
    (net (code "66") (name "VIN") (class "Default")
      (node (ref "5VREG") (pin "1") (pinfunction "IN_1") (pintype "input"))
      (node (ref "C15") (pin "A") (pinfunction "+_A") (pintype "passive"))
      (node (ref "D5") (pin "3") (pinfunction "C_3") (pintype "passive"))
    )
    (net (code "67") (name "VUSB") (class "Default")
      (node (ref "C11") (pin "A") (pinfunction "+_A") (pintype "passive"))
      (node (ref "C5") (pin "1") (pinfunction "1_1") (pintype "passive"))
      (node (ref "FB3") (pin "1") (pinfunction "1_1") (pintype "passive"))
      (node (ref "FB3") (pin "2") (pinfunction "2_2") (pintype "passive"))
      (node (ref "FTD231X") (pin "15") (pinfunction "VCC_15") (pintype "bidirectional"))
      (node (ref "J2") (pin "VCC") (pinfunction "VBUS_VCC") (pintype "power_in"))
    )
    (net (code "68") (name "unconnected-(FTD231X-CBUS0-Pad18)") (class "Default")
      (node (ref "FTD231X") (pin "18") (pinfunction "CBUS0_18") (pintype "bidirectional"))
    )
    (net (code "69") (name "unconnected-(FTD231X-CBUS3-Pad19)") (class "Default")
      (node (ref "FTD231X") (pin "19") (pinfunction "CBUS3_19") (pintype "bidirectional"))
    )
    (net (code "70") (name "unconnected-(FTD231X-~{CTS}-Pad9)") (class "Default")
      (node (ref "FTD231X") (pin "9") (pinfunction "~{CTS}_9") (pintype "bidirectional"))
    )
    (net (code "71") (name "unconnected-(FTD231X-~{DCD}-Pad8)") (class "Default")
      (node (ref "FTD231X") (pin "8") (pinfunction "~{DCD}_8") (pintype "bidirectional"))
    )
    (net (code "72") (name "unconnected-(FTD231X-~{DSR}-Pad7)") (class "Default")
      (node (ref "FTD231X") (pin "7") (pinfunction "~{DSR}_7") (pintype "bidirectional"))
    )
    (net (code "73") (name "unconnected-(FTD231X-~{RI}-Pad5)") (class "Default")
      (node (ref "FTD231X") (pin "5") (pinfunction "~{RI}_5") (pintype "bidirectional"))
    )
    (net (code "74") (name "unconnected-(FTD231X-~{RTS}-Pad2)") (class "Default")
      (node (ref "FTD231X") (pin "2") (pinfunction "~{RTS}_2") (pintype "bidirectional"))
    )
    (net (code "75") (name "unconnected-(J1-Pad1)") (class "Default")
      (node (ref "J1") (pin "1") (pinfunction "1_1") (pintype "passive"))
    )
    (net (code "76") (name "unconnected-(J1-Pad2)") (class "Default")
      (node (ref "J1") (pin "2") (pinfunction "2_2") (pintype "passive"))
    )
    (net (code "77") (name "unconnected-(J1-Pad3)") (class "Default")
      (node (ref "J1") (pin "3") (pinfunction "3_3") (pintype "passive"))
    )
    (net (code "78") (name "unconnected-(J2-PadID)") (class "Default")
      (node (ref "J2") (pin "ID") (pinfunction "ID_ID") (pintype "bidirectional"))
    )
    (net (code "79") (name "unconnected-(J8-Pad2)") (class "Default")
      (node (ref "J8") (pin "2") (pinfunction "2_2") (pintype "passive"))
    )
    (net (code "80") (name "unconnected-(J8-Pad3)") (class "Default")
      (node (ref "J8") (pin "3") (pinfunction "3_3") (pintype "passive"))
    )
    (net (code "81") (name "unconnected-(J8-Pad13)") (class "Default")
      (node (ref "J8") (pin "13") (pinfunction "13_13") (pintype "passive"))
    )
    (net (code "82") (name "unconnected-(J8-Pad14)") (class "Default")
      (node (ref "J8") (pin "14") (pinfunction "14_14") (pintype "passive"))
    )
    (net (code "83") (name "unconnected-(J8-Pad15)") (class "Default")
      (node (ref "J8") (pin "15") (pinfunction "15_15") (pintype "passive"))
    )
    (net (code "84") (name "unconnected-(MPU6050-AUX_CL-Pad7)") (class "Default")
      (node (ref "MPU6050") (pin "7") (pinfunction "AUX_CL_7") (pintype "bidirectional"))
    )
    (net (code "85") (name "unconnected-(MPU6050-AUX_DA-Pad6)") (class "Default")
      (node (ref "MPU6050") (pin "6") (pinfunction "AUX_DA_6") (pintype "bidirectional"))
    )
    (net (code "86") (name "unconnected-(MPU6050-CLKIN-Pad1)") (class "Default")
      (node (ref "MPU6050") (pin "1") (pinfunction "CLKIN_1") (pintype "bidirectional"))
    )
    (net (code "87") (name "unconnected-(MPU6050-FYSNC-Pad11)") (class "Default")
      (node (ref "MPU6050") (pin "11") (pinfunction "FYSNC_11") (pintype "bidirectional"))
    )
    (net (code "88") (name "unconnected-(U$2-CD{slash}DAT3-PadCD{slash}DAT3{slash}SS{slash}CS)") (class "Default")
      (node (ref "U$2") (pin "CD/DAT3/SS/CS") (pinfunction "CD/DAT3_CD/DAT3/SS/CS") (pintype "bidirectional"))
    )
    (net (code "89") (name "unconnected-(U$2-PadDAT2)") (class "Default")
      (node (ref "U$2") (pin "DAT2") (pinfunction "DAT2_DAT2") (pintype "bidirectional"))
    )
  )
)
